# picoKey_230406.net
KiCad netlist of a schematic drawn in EAGLE
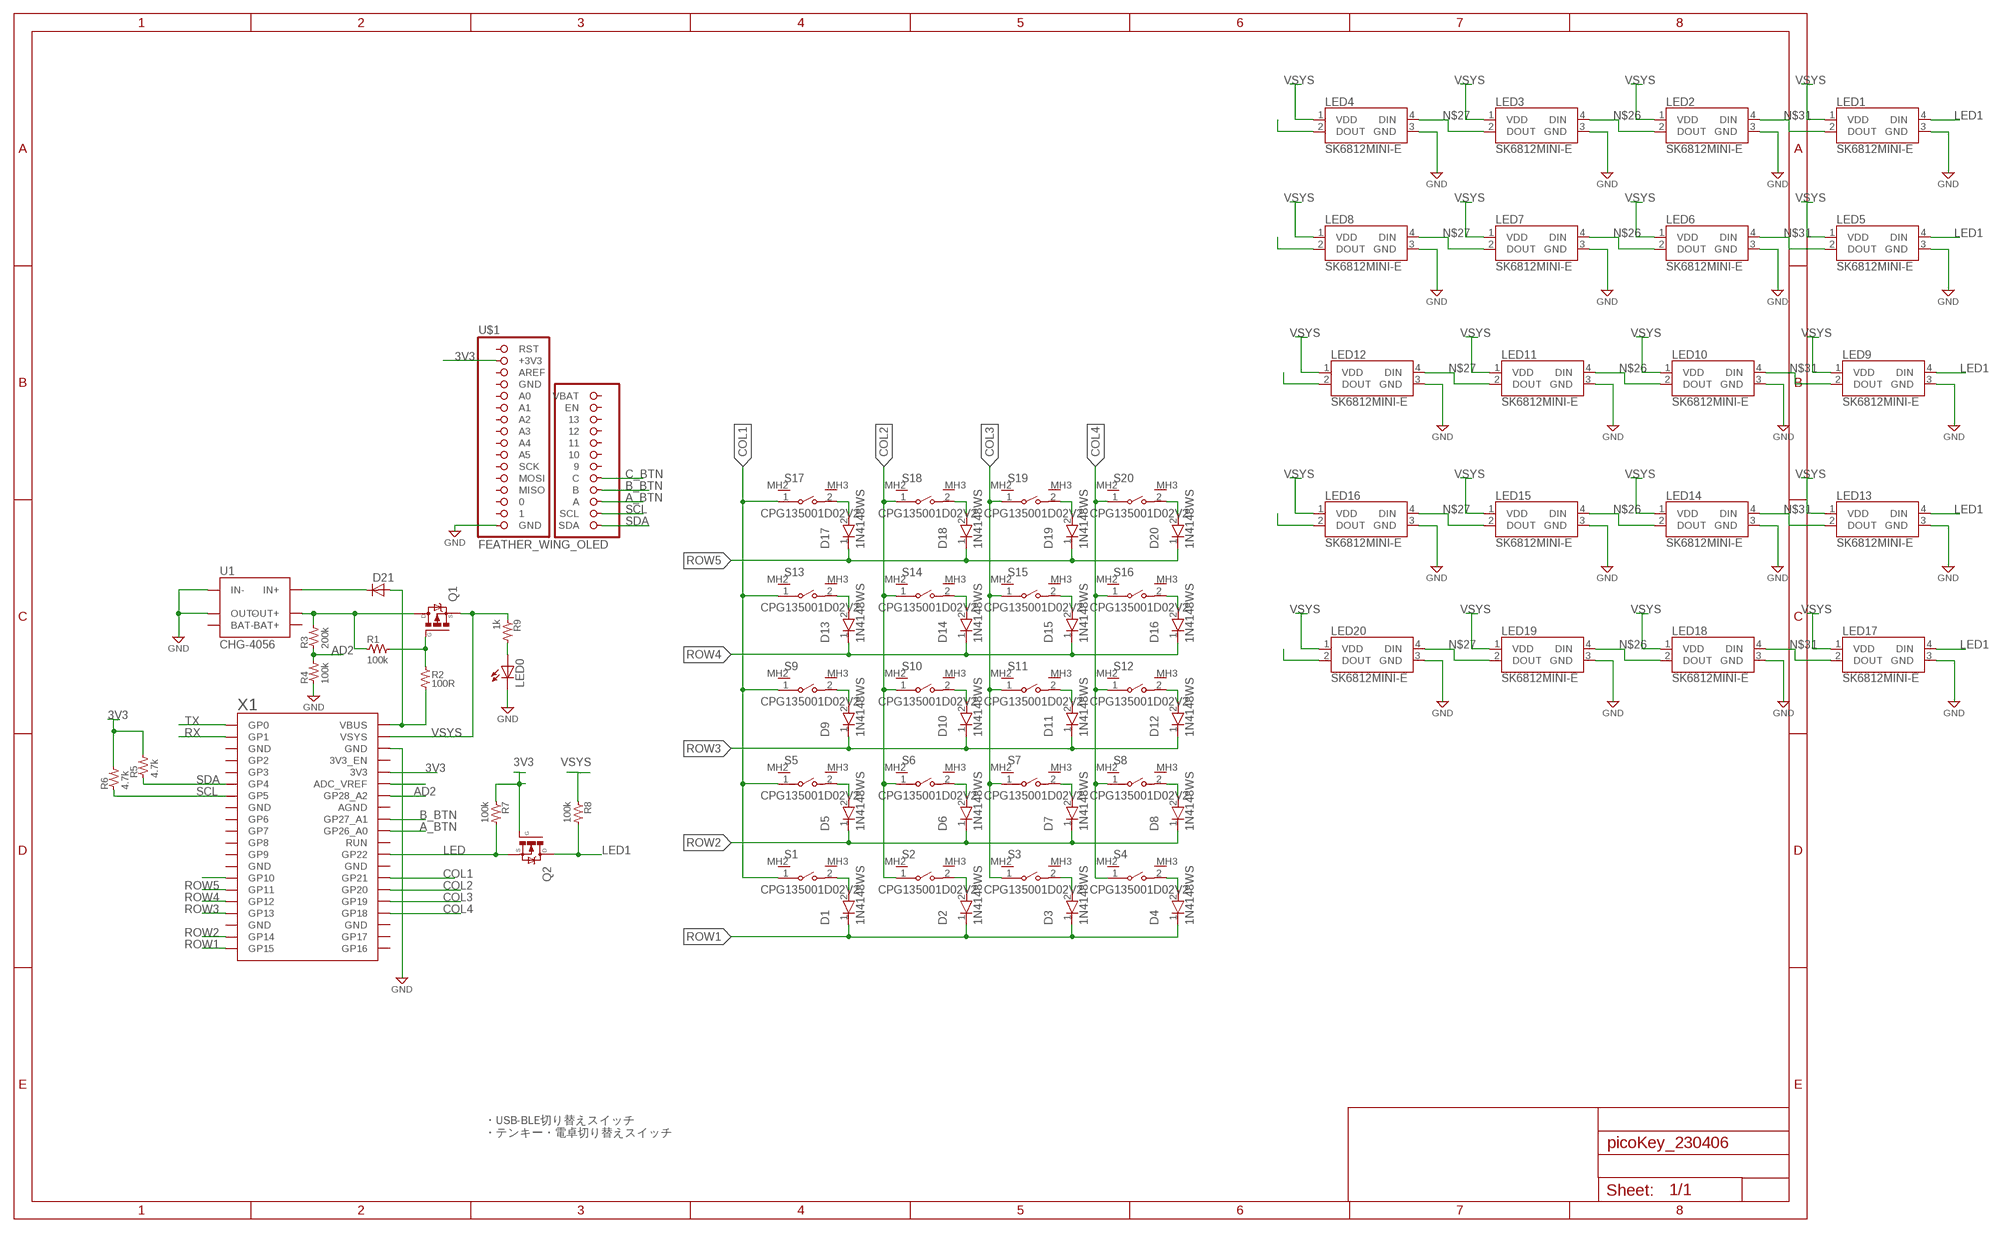
[diagram p0: schematic, sheet 1]

(export (version "E")
  (design (tool "Eeschema 10.0.6"))
  (components
    (comp (ref "D1")
      (value "1N4148WS")
      (footprint "eagle-import:SODFL2512X90N")
      (fields (field (name "MOUSER_PART_NUMBER") "512-1N4148WS"))
      (libsource (lib "eagle-import") (part "1N4148WS"))
    )
    (comp (ref "D2")
      (value "1N4148WS")
      (footprint "eagle-import:SODFL2512X90N")
      (fields (field (name "MOUSER_PART_NUMBER") "512-1N4148WS"))
      (libsource (lib "eagle-import") (part "1N4148WS"))
    )
    (comp (ref "D3")
      (value "1N4148WS")
      (footprint "eagle-import:SODFL2512X90N")
      (fields (field (name "MOUSER_PART_NUMBER") "512-1N4148WS"))
      (libsource (lib "eagle-import") (part "1N4148WS"))
    )
    (comp (ref "D4")
      (value "1N4148WS")
      (footprint "eagle-import:SODFL2512X90N")
      (fields (field (name "MOUSER_PART_NUMBER") "512-1N4148WS"))
      (libsource (lib "eagle-import") (part "1N4148WS"))
    )
    (comp (ref "D5")
      (value "1N4148WS")
      (footprint "eagle-import:SODFL2512X90N")
      (fields (field (name "MOUSER_PART_NUMBER") "512-1N4148WS"))
      (libsource (lib "eagle-import") (part "1N4148WS"))
    )
    (comp (ref "D6")
      (value "1N4148WS")
      (footprint "eagle-import:SODFL2512X90N")
      (fields (field (name "MOUSER_PART_NUMBER") "512-1N4148WS"))
      (libsource (lib "eagle-import") (part "1N4148WS"))
    )
    (comp (ref "D7")
      (value "1N4148WS")
      (footprint "eagle-import:SODFL2512X90N")
      (fields (field (name "MOUSER_PART_NUMBER") "512-1N4148WS"))
      (libsource (lib "eagle-import") (part "1N4148WS"))
    )
    (comp (ref "D8")
      (value "1N4148WS")
      (footprint "eagle-import:SODFL2512X90N")
      (fields (field (name "MOUSER_PART_NUMBER") "512-1N4148WS"))
      (libsource (lib "eagle-import") (part "1N4148WS"))
    )
    (comp (ref "D9")
      (value "1N4148WS")
      (footprint "eagle-import:SODFL2512X90N")
      (fields (field (name "MOUSER_PART_NUMBER") "512-1N4148WS"))
      (libsource (lib "eagle-import") (part "1N4148WS"))
    )
    (comp (ref "D10")
      (value "1N4148WS")
      (footprint "eagle-import:SODFL2512X90N")
      (fields (field (name "MOUSER_PART_NUMBER") "512-1N4148WS"))
      (libsource (lib "eagle-import") (part "1N4148WS"))
    )
    (comp (ref "D11")
      (value "1N4148WS")
      (footprint "eagle-import:SODFL2512X90N")
      (fields (field (name "MOUSER_PART_NUMBER") "512-1N4148WS"))
      (libsource (lib "eagle-import") (part "1N4148WS"))
    )
    (comp (ref "D12")
      (value "1N4148WS")
      (footprint "eagle-import:SODFL2512X90N")
      (fields (field (name "MOUSER_PART_NUMBER") "512-1N4148WS"))
      (libsource (lib "eagle-import") (part "1N4148WS"))
    )
    (comp (ref "D13")
      (value "1N4148WS")
      (footprint "eagle-import:SODFL2512X90N")
      (fields (field (name "MOUSER_PART_NUMBER") "512-1N4148WS"))
      (libsource (lib "eagle-import") (part "1N4148WS"))
    )
    (comp (ref "D14")
      (value "1N4148WS")
      (footprint "eagle-import:SODFL2512X90N")
      (fields (field (name "MOUSER_PART_NUMBER") "512-1N4148WS"))
      (libsource (lib "eagle-import") (part "1N4148WS"))
    )
    (comp (ref "D15")
      (value "1N4148WS")
      (footprint "eagle-import:SODFL2512X90N")
      (fields (field (name "MOUSER_PART_NUMBER") "512-1N4148WS"))
      (libsource (lib "eagle-import") (part "1N4148WS"))
    )
    (comp (ref "D16")
      (value "1N4148WS")
      (footprint "eagle-import:SODFL2512X90N")
      (fields (field (name "MOUSER_PART_NUMBER") "512-1N4148WS"))
      (libsource (lib "eagle-import") (part "1N4148WS"))
    )
    (comp (ref "D17")
      (value "1N4148WS")
      (footprint "eagle-import:SODFL2512X90N")
      (fields (field (name "MOUSER_PART_NUMBER") "512-1N4148WS"))
      (libsource (lib "eagle-import") (part "1N4148WS"))
    )
    (comp (ref "D18")
      (value "1N4148WS")
      (footprint "eagle-import:SODFL2512X90N")
      (fields (field (name "MOUSER_PART_NUMBER") "512-1N4148WS"))
      (libsource (lib "eagle-import") (part "1N4148WS"))
    )
    (comp (ref "D19")
      (value "1N4148WS")
      (footprint "eagle-import:SODFL2512X90N")
      (fields (field (name "MOUSER_PART_NUMBER") "512-1N4148WS"))
      (libsource (lib "eagle-import") (part "1N4148WS"))
    )
    (comp (ref "D20")
      (value "1N4148WS")
      (footprint "eagle-import:SODFL2512X90N")
      (fields (field (name "MOUSER_PART_NUMBER") "512-1N4148WS"))
      (libsource (lib "eagle-import") (part "1N4148WS"))
    )
    (comp (ref "D21")
      (value "DIODE123")
      (footprint "eagle-import:SOD-123")
      (libsource (lib "eagle-import") (part "DIODE123"))
    )
    (comp (ref "LED0")
      (value "LEDCHIP-LED0603")
      (footprint "eagle-import:CHIP-LED0603")
      (libsource (lib "eagle-import") (part "LEDCHIP-LED0603"))
    )
    (comp (ref "LED1")
      (value "SK6812MINI-E")
      (footprint "eagle-import:SK6812MINIE")
      (libsource (lib "eagle-import") (part "SK6812MINI-E"))
    )
    (comp (ref "LED2")
      (value "SK6812MINI-E")
      (footprint "eagle-import:SK6812MINIE")
      (libsource (lib "eagle-import") (part "SK6812MINI-E"))
    )
    (comp (ref "LED3")
      (value "SK6812MINI-E")
      (footprint "eagle-import:SK6812MINIE")
      (libsource (lib "eagle-import") (part "SK6812MINI-E"))
    )
    (comp (ref "LED4")
      (value "SK6812MINI-E")
      (footprint "eagle-import:SK6812MINIE")
      (libsource (lib "eagle-import") (part "SK6812MINI-E"))
    )
    (comp (ref "LED5")
      (value "SK6812MINI-E")
      (footprint "eagle-import:SK6812MINIE")
      (libsource (lib "eagle-import") (part "SK6812MINI-E"))
    )
    (comp (ref "LED6")
      (value "SK6812MINI-E")
      (footprint "eagle-import:SK6812MINIE")
      (libsource (lib "eagle-import") (part "SK6812MINI-E"))
    )
    (comp (ref "LED7")
      (value "SK6812MINI-E")
      (footprint "eagle-import:SK6812MINIE")
      (libsource (lib "eagle-import") (part "SK6812MINI-E"))
    )
    (comp (ref "LED8")
      (value "SK6812MINI-E")
      (footprint "eagle-import:SK6812MINIE")
      (libsource (lib "eagle-import") (part "SK6812MINI-E"))
    )
    (comp (ref "LED9")
      (value "SK6812MINI-E")
      (footprint "eagle-import:SK6812MINIE")
      (libsource (lib "eagle-import") (part "SK6812MINI-E"))
    )
    (comp (ref "LED10")
      (value "SK6812MINI-E")
      (footprint "eagle-import:SK6812MINIE")
      (libsource (lib "eagle-import") (part "SK6812MINI-E"))
    )
    (comp (ref "LED11")
      (value "SK6812MINI-E")
      (footprint "eagle-import:SK6812MINIE")
      (libsource (lib "eagle-import") (part "SK6812MINI-E"))
    )
    (comp (ref "LED12")
      (value "SK6812MINI-E")
      (footprint "eagle-import:SK6812MINIE")
      (libsource (lib "eagle-import") (part "SK6812MINI-E"))
    )
    (comp (ref "LED13")
      (value "SK6812MINI-E")
      (footprint "eagle-import:SK6812MINIE")
      (libsource (lib "eagle-import") (part "SK6812MINI-E"))
    )
    (comp (ref "LED14")
      (value "SK6812MINI-E")
      (footprint "eagle-import:SK6812MINIE")
      (libsource (lib "eagle-import") (part "SK6812MINI-E"))
    )
    (comp (ref "LED15")
      (value "SK6812MINI-E")
      (footprint "eagle-import:SK6812MINIE")
      (libsource (lib "eagle-import") (part "SK6812MINI-E"))
    )
    (comp (ref "LED16")
      (value "SK6812MINI-E")
      (footprint "eagle-import:SK6812MINIE")
      (libsource (lib "eagle-import") (part "SK6812MINI-E"))
    )
    (comp (ref "LED17")
      (value "SK6812MINI-E")
      (footprint "eagle-import:SK6812MINIE")
      (libsource (lib "eagle-import") (part "SK6812MINI-E"))
    )
    (comp (ref "LED18")
      (value "SK6812MINI-E")
      (footprint "eagle-import:SK6812MINIE")
      (libsource (lib "eagle-import") (part "SK6812MINI-E"))
    )
    (comp (ref "LED19")
      (value "SK6812MINI-E")
      (footprint "eagle-import:SK6812MINIE")
      (libsource (lib "eagle-import") (part "SK6812MINI-E"))
    )
    (comp (ref "LED20")
      (value "SK6812MINI-E")
      (footprint "eagle-import:SK6812MINIE")
      (libsource (lib "eagle-import") (part "SK6812MINI-E"))
    )
    (comp (ref "Q1")
      (value "MOSFET-P")
      (footprint "eagle-import:SOT-23")
      (libsource (lib "eagle-import") (part "MOSFET-P"))
    )
    (comp (ref "Q2")
      (value "MOSFET-NSOT-23")
      (footprint "eagle-import:SOT-23")
      (libsource (lib "eagle-import") (part "MOSFET-NSOT-23"))
    )
    (comp (ref "R1")
      (value "100k")
      (footprint "eagle-import:R0603")
      (libsource (lib "eagle-import") (part "R_0603"))
    )
    (comp (ref "R2")
      (value "100R")
      (footprint "eagle-import:R0603")
      (libsource (lib "eagle-import") (part "R_0603"))
    )
    (comp (ref "R3")
      (value "200k")
      (footprint "eagle-import:R0603")
      (libsource (lib "eagle-import") (part "R_0603"))
    )
    (comp (ref "R4")
      (value "100k")
      (footprint "eagle-import:R0603")
      (libsource (lib "eagle-import") (part "R_0603"))
    )
    (comp (ref "R5")
      (value "4.7k")
      (footprint "eagle-import:R0603")
      (libsource (lib "eagle-import") (part "R_0603"))
    )
    (comp (ref "R6")
      (value "4.7k")
      (footprint "eagle-import:R0603")
      (libsource (lib "eagle-import") (part "R_0603"))
    )
    (comp (ref "R7")
      (value "100k")
      (footprint "eagle-import:R0603")
      (libsource (lib "eagle-import") (part "R_0603"))
    )
    (comp (ref "R8")
      (value "100k")
      (footprint "eagle-import:R0603")
      (libsource (lib "eagle-import") (part "R_0603"))
    )
    (comp (ref "R9")
      (value "1k")
      (footprint "eagle-import:R0603")
      (libsource (lib "eagle-import") (part "R_0603"))
    )
    (comp (ref "S1")
      (value "CPG135001D02V2")
      (footprint "eagle-import:KAILH_CHOC_V2")
      (libsource (lib "eagle-import") (part "CPG135001D02V2"))
    )
    (comp (ref "S2")
      (value "CPG135001D02V2")
      (footprint "eagle-import:KAILH_CHOC_V2")
      (libsource (lib "eagle-import") (part "CPG135001D02V2"))
    )
    (comp (ref "S3")
      (value "CPG135001D02V2")
      (footprint "eagle-import:KAILH_CHOC_V2")
      (libsource (lib "eagle-import") (part "CPG135001D02V2"))
    )
    (comp (ref "S4")
      (value "CPG135001D02V2")
      (footprint "eagle-import:KAILH_CHOC_V2")
      (libsource (lib "eagle-import") (part "CPG135001D02V2"))
    )
    (comp (ref "S5")
      (value "CPG135001D02V2")
      (footprint "eagle-import:KAILH_CHOC_V2")
      (libsource (lib "eagle-import") (part "CPG135001D02V2"))
    )
    (comp (ref "S6")
      (value "CPG135001D02V2")
      (footprint "eagle-import:KAILH_CHOC_V2")
      (libsource (lib "eagle-import") (part "CPG135001D02V2"))
    )
    (comp (ref "S7")
      (value "CPG135001D02V2")
      (footprint "eagle-import:KAILH_CHOC_V2")
      (libsource (lib "eagle-import") (part "CPG135001D02V2"))
    )
    (comp (ref "S8")
      (value "CPG135001D02V2")
      (footprint "eagle-import:KAILH_CHOC_V2")
      (libsource (lib "eagle-import") (part "CPG135001D02V2"))
    )
    (comp (ref "S9")
      (value "CPG135001D02V2")
      (footprint "eagle-import:KAILH_CHOC_V2")
      (libsource (lib "eagle-import") (part "CPG135001D02V2"))
    )
    (comp (ref "S10")
      (value "CPG135001D02V2")
      (footprint "eagle-import:KAILH_CHOC_V2")
      (libsource (lib "eagle-import") (part "CPG135001D02V2"))
    )
    (comp (ref "S11")
      (value "CPG135001D02V2")
      (footprint "eagle-import:KAILH_CHOC_V2")
      (libsource (lib "eagle-import") (part "CPG135001D02V2"))
    )
    (comp (ref "S12")
      (value "CPG135001D02V2")
      (footprint "eagle-import:KAILH_CHOC_V2")
      (libsource (lib "eagle-import") (part "CPG135001D02V2"))
    )
    (comp (ref "S13")
      (value "CPG135001D02V2")
      (footprint "eagle-import:KAILH_CHOC_V2")
      (libsource (lib "eagle-import") (part "CPG135001D02V2"))
    )
    (comp (ref "S14")
      (value "CPG135001D02V2")
      (footprint "eagle-import:KAILH_CHOC_V2")
      (libsource (lib "eagle-import") (part "CPG135001D02V2"))
    )
    (comp (ref "S15")
      (value "CPG135001D02V2")
      (footprint "eagle-import:KAILH_CHOC_V2")
      (libsource (lib "eagle-import") (part "CPG135001D02V2"))
    )
    (comp (ref "S16")
      (value "CPG135001D02V2")
      (footprint "eagle-import:KAILH_CHOC_V2")
      (libsource (lib "eagle-import") (part "CPG135001D02V2"))
    )
    (comp (ref "S17")
      (value "CPG135001D02V2")
      (footprint "eagle-import:KAILH_CHOC_V2")
      (libsource (lib "eagle-import") (part "CPG135001D02V2"))
    )
    (comp (ref "S18")
      (value "CPG135001D02V2")
      (footprint "eagle-import:KAILH_CHOC_V2")
      (libsource (lib "eagle-import") (part "CPG135001D02V2"))
    )
    (comp (ref "S19")
      (value "CPG135001D02V2")
      (footprint "eagle-import:KAILH_CHOC_V2")
      (libsource (lib "eagle-import") (part "CPG135001D02V2"))
    )
    (comp (ref "S20")
      (value "CPG135001D02V2")
      (footprint "eagle-import:KAILH_CHOC_V2")
      (libsource (lib "eagle-import") (part "CPG135001D02V2"))
    )
    (comp (ref "U$1")
      (value "FEATHER_WING_OLED")
      (footprint "eagle-import:FEATHER_WING_OLED")
      (libsource (lib "eagle-import") (part "FEATHER_WING_OLED"))
    )
    (comp (ref "U1")
      (value "CHG-4056")
      (footprint "eagle-import:CHG-4056")
      (libsource (lib "eagle-import") (part "CHG-4056"))
    )
    (comp (ref "X1")
      (value "RASPBERRYPI_PICO_RPI_PICO_MY-MY")
      (footprint "eagle-import:RASPBERRYPI_PICO_RPI_PICO_MY")
      (libsource (lib "eagle-import") (part "RASPBERRYPI_PICO_RPI_PICO_MY-MY"))
    )
  )
  (nets
    (net (code "1") (name "/3V3") (class "Default")
      (node (ref "Q2") (pin "3") (pinfunction "G_3") (pintype "passive"))
      (node (ref "R5") (pin "2") (pinfunction "2_2") (pintype "passive"))
      (node (ref "R6") (pin "2") (pinfunction "2_2") (pintype "passive"))
      (node (ref "R7") (pin "1") (pinfunction "1_1") (pintype "passive"))
      (node (ref "U$1") (pin "15") (pinfunction "+3V3_15") (pintype "passive"))
      (node (ref "X1") (pin "3V3") (pinfunction "3V3_3V3") (pintype "bidirectional"))
    )
    (net (code "2") (name "/AD2") (class "Default")
      (node (ref "R3") (pin "1") (pinfunction "1_1") (pintype "passive"))
      (node (ref "R4") (pin "2") (pinfunction "2_2") (pintype "passive"))
      (node (ref "X1") (pin "GP28_A2") (pinfunction "GP28_A2_GP28_A2") (pintype "bidirectional"))
    )
    (net (code "3") (name "/A_BTN") (class "Default")
      (node (ref "U$1") (pin "26") (pinfunction "A_26") (pintype "passive"))
      (node (ref "X1") (pin "GP26_A0") (pinfunction "GP26_A0_GP26_A0") (pintype "bidirectional"))
    )
    (net (code "4") (name "/B_BTN") (class "Default")
      (node (ref "U$1") (pin "25") (pinfunction "B_25") (pintype "passive"))
      (node (ref "X1") (pin "GP27_A1") (pinfunction "GP27_A1_GP27_A1") (pintype "bidirectional"))
    )
    (net (code "5") (name "/C_BTN") (class "Default")
      (node (ref "U$1") (pin "24") (pinfunction "C_24") (pintype "passive"))
    )
    (net (code "6") (name "/LED") (class "Default")
      (node (ref "Q2") (pin "1") (pinfunction "S_1") (pintype "passive"))
      (node (ref "R7") (pin "2") (pinfunction "2_2") (pintype "passive"))
      (node (ref "X1") (pin "GP22") (pinfunction "GP22_GP22") (pintype "bidirectional"))
    )
    (net (code "7") (name "/LED1") (class "Default")
      (node (ref "LED1") (pin "4") (pinfunction "DIN_4") (pintype "bidirectional"))
      (node (ref "LED13") (pin "4") (pinfunction "DIN_4") (pintype "bidirectional"))
      (node (ref "LED17") (pin "4") (pinfunction "DIN_4") (pintype "bidirectional"))
      (node (ref "LED5") (pin "4") (pinfunction "DIN_4") (pintype "bidirectional"))
      (node (ref "LED9") (pin "4") (pinfunction "DIN_4") (pintype "bidirectional"))
      (node (ref "Q2") (pin "2") (pinfunction "D_2") (pintype "passive"))
      (node (ref "R8") (pin "2") (pinfunction "2_2") (pintype "passive"))
    )
    (net (code "8") (name "/N$26") (class "Default")
      (node (ref "LED10") (pin "2") (pinfunction "DOUT_2") (pintype "bidirectional"))
      (node (ref "LED11") (pin "4") (pinfunction "DIN_4") (pintype "bidirectional"))
      (node (ref "LED14") (pin "2") (pinfunction "DOUT_2") (pintype "bidirectional"))
      (node (ref "LED15") (pin "4") (pinfunction "DIN_4") (pintype "bidirectional"))
      (node (ref "LED18") (pin "2") (pinfunction "DOUT_2") (pintype "bidirectional"))
      (node (ref "LED19") (pin "4") (pinfunction "DIN_4") (pintype "bidirectional"))
      (node (ref "LED2") (pin "2") (pinfunction "DOUT_2") (pintype "bidirectional"))
      (node (ref "LED3") (pin "4") (pinfunction "DIN_4") (pintype "bidirectional"))
      (node (ref "LED6") (pin "2") (pinfunction "DOUT_2") (pintype "bidirectional"))
      (node (ref "LED7") (pin "4") (pinfunction "DIN_4") (pintype "bidirectional"))
    )
    (net (code "9") (name "/N$27") (class "Default")
      (node (ref "LED11") (pin "2") (pinfunction "DOUT_2") (pintype "bidirectional"))
      (node (ref "LED12") (pin "4") (pinfunction "DIN_4") (pintype "bidirectional"))
      (node (ref "LED15") (pin "2") (pinfunction "DOUT_2") (pintype "bidirectional"))
      (node (ref "LED16") (pin "4") (pinfunction "DIN_4") (pintype "bidirectional"))
      (node (ref "LED19") (pin "2") (pinfunction "DOUT_2") (pintype "bidirectional"))
      (node (ref "LED20") (pin "4") (pinfunction "DIN_4") (pintype "bidirectional"))
      (node (ref "LED3") (pin "2") (pinfunction "DOUT_2") (pintype "bidirectional"))
      (node (ref "LED4") (pin "4") (pinfunction "DIN_4") (pintype "bidirectional"))
      (node (ref "LED7") (pin "2") (pinfunction "DOUT_2") (pintype "bidirectional"))
      (node (ref "LED8") (pin "4") (pinfunction "DIN_4") (pintype "bidirectional"))
    )
    (net (code "10") (name "/N$31") (class "Default")
      (node (ref "LED1") (pin "2") (pinfunction "DOUT_2") (pintype "bidirectional"))
      (node (ref "LED10") (pin "4") (pinfunction "DIN_4") (pintype "bidirectional"))
      (node (ref "LED13") (pin "2") (pinfunction "DOUT_2") (pintype "bidirectional"))
      (node (ref "LED14") (pin "4") (pinfunction "DIN_4") (pintype "bidirectional"))
      (node (ref "LED17") (pin "2") (pinfunction "DOUT_2") (pintype "bidirectional"))
      (node (ref "LED18") (pin "4") (pinfunction "DIN_4") (pintype "bidirectional"))
      (node (ref "LED2") (pin "4") (pinfunction "DIN_4") (pintype "bidirectional"))
      (node (ref "LED5") (pin "2") (pinfunction "DOUT_2") (pintype "bidirectional"))
      (node (ref "LED6") (pin "4") (pinfunction "DIN_4") (pintype "bidirectional"))
      (node (ref "LED9") (pin "2") (pinfunction "DOUT_2") (pintype "bidirectional"))
    )
    (net (code "11") (name "/RX") (class "Default")
      (node (ref "X1") (pin "GP1") (pinfunction "GP1_GP1") (pintype "bidirectional"))
    )
    (net (code "12") (name "/SCL") (class "Default")
      (node (ref "R6") (pin "1") (pinfunction "1_1") (pintype "passive"))
      (node (ref "U$1") (pin "27") (pinfunction "SCL_27") (pintype "passive"))
      (node (ref "X1") (pin "GP5") (pinfunction "GP5_GP5") (pintype "bidirectional"))
    )
    (net (code "13") (name "/SDA") (class "Default")
      (node (ref "R5") (pin "1") (pinfunction "1_1") (pintype "passive"))
      (node (ref "U$1") (pin "28") (pinfunction "SDA_28") (pintype "passive"))
      (node (ref "X1") (pin "GP4") (pinfunction "GP4_GP4") (pintype "bidirectional"))
    )
    (net (code "14") (name "/TX") (class "Default")
      (node (ref "X1") (pin "GP0") (pinfunction "GP0_GP0") (pintype "bidirectional"))
    )
    (net (code "15") (name "/VSYS") (class "Default")
      (node (ref "LED1") (pin "1") (pinfunction "VDD_1") (pintype "bidirectional"))
      (node (ref "LED10") (pin "1") (pinfunction "VDD_1") (pintype "bidirectional"))
      (node (ref "LED11") (pin "1") (pinfunction "VDD_1") (pintype "bidirectional"))
      (node (ref "LED12") (pin "1") (pinfunction "VDD_1") (pintype "bidirectional"))
      (node (ref "LED13") (pin "1") (pinfunction "VDD_1") (pintype "bidirectional"))
      (node (ref "LED14") (pin "1") (pinfunction "VDD_1") (pintype "bidirectional"))
      (node (ref "LED15") (pin "1") (pinfunction "VDD_1") (pintype "bidirectional"))
      (node (ref "LED16") (pin "1") (pinfunction "VDD_1") (pintype "bidirectional"))
      (node (ref "LED17") (pin "1") (pinfunction "VDD_1") (pintype "bidirectional"))
      (node (ref "LED18") (pin "1") (pinfunction "VDD_1") (pintype "bidirectional"))
      (node (ref "LED19") (pin "1") (pinfunction "VDD_1") (pintype "bidirectional"))
      (node (ref "LED2") (pin "1") (pinfunction "VDD_1") (pintype "bidirectional"))
      (node (ref "LED20") (pin "1") (pinfunction "VDD_1") (pintype "bidirectional"))
      (node (ref "LED3") (pin "1") (pinfunction "VDD_1") (pintype "bidirectional"))
      (node (ref "LED4") (pin "1") (pinfunction "VDD_1") (pintype "bidirectional"))
      (node (ref "LED5") (pin "1") (pinfunction "VDD_1") (pintype "bidirectional"))
      (node (ref "LED6") (pin "1") (pinfunction "VDD_1") (pintype "bidirectional"))
      (node (ref "LED7") (pin "1") (pinfunction "VDD_1") (pintype "bidirectional"))
      (node (ref "LED8") (pin "1") (pinfunction "VDD_1") (pintype "bidirectional"))
      (node (ref "LED9") (pin "1") (pinfunction "VDD_1") (pintype "bidirectional"))
      (node (ref "Q1") (pin "1") (pinfunction "S_1") (pintype "passive"))
      (node (ref "R8") (pin "1") (pinfunction "1_1") (pintype "passive"))
      (node (ref "R9") (pin "1") (pinfunction "1_1") (pintype "passive"))
      (node (ref "X1") (pin "VSYS") (pinfunction "VSYS_VSYS") (pintype "bidirectional"))
    )
    (net (code "16") (name "COL1") (class "Default")
      (node (ref "S1") (pin "1") (pinfunction "1_1") (pintype "bidirectional"))
      (node (ref "S13") (pin "1") (pinfunction "1_1") (pintype "bidirectional"))
      (node (ref "S17") (pin "1") (pinfunction "1_1") (pintype "bidirectional"))
      (node (ref "S5") (pin "1") (pinfunction "1_1") (pintype "bidirectional"))
      (node (ref "S9") (pin "1") (pinfunction "1_1") (pintype "bidirectional"))
      (node (ref "X1") (pin "GP21") (pinfunction "GP21_GP21") (pintype "bidirectional"))
    )
    (net (code "17") (name "COL2") (class "Default")
      (node (ref "S10") (pin "1") (pinfunction "1_1") (pintype "bidirectional"))
      (node (ref "S14") (pin "1") (pinfunction "1_1") (pintype "bidirectional"))
      (node (ref "S18") (pin "1") (pinfunction "1_1") (pintype "bidirectional"))
      (node (ref "S2") (pin "1") (pinfunction "1_1") (pintype "bidirectional"))
      (node (ref "S6") (pin "1") (pinfunction "1_1") (pintype "bidirectional"))
      (node (ref "X1") (pin "GP20") (pinfunction "GP20_GP20") (pintype "bidirectional"))
    )
    (net (code "18") (name "COL3") (class "Default")
      (node (ref "S11") (pin "1") (pinfunction "1_1") (pintype "bidirectional"))
      (node (ref "S15") (pin "1") (pinfunction "1_1") (pintype "bidirectional"))
      (node (ref "S19") (pin "1") (pinfunction "1_1") (pintype "bidirectional"))
      (node (ref "S3") (pin "1") (pinfunction "1_1") (pintype "bidirectional"))
      (node (ref "S7") (pin "1") (pinfunction "1_1") (pintype "bidirectional"))
      (node (ref "X1") (pin "GP19") (pinfunction "GP19_GP19") (pintype "bidirectional"))
    )
    (net (code "19") (name "COL4") (class "Default")
      (node (ref "S12") (pin "1") (pinfunction "1_1") (pintype "bidirectional"))
      (node (ref "S16") (pin "1") (pinfunction "1_1") (pintype "bidirectional"))
      (node (ref "S20") (pin "1") (pinfunction "1_1") (pintype "bidirectional"))
      (node (ref "S4") (pin "1") (pinfunction "1_1") (pintype "bidirectional"))
      (node (ref "S8") (pin "1") (pinfunction "1_1") (pintype "bidirectional"))
      (node (ref "X1") (pin "GP18") (pinfunction "GP18_GP18") (pintype "bidirectional"))
    )
    (net (code "20") (name "G") (class "Default")
      (node (ref "LED0") (pin "C") (pinfunction "C_C") (pintype "passive"))
      (node (ref "LED1") (pin "3") (pinfunction "GND_3") (pintype "bidirectional"))
      (node (ref "LED10") (pin "3") (pinfunction "GND_3") (pintype "bidirectional"))
      (node (ref "LED11") (pin "3") (pinfunction "GND_3") (pintype "bidirectional"))
      (node (ref "LED12") (pin "3") (pinfunction "GND_3") (pintype "bidirectional"))
      (node (ref "LED13") (pin "3") (pinfunction "GND_3") (pintype "bidirectional"))
      (node (ref "LED14") (pin "3") (pinfunction "GND_3") (pintype "bidirectional"))
      (node (ref "LED15") (pin "3") (pinfunction "GND_3") (pintype "bidirectional"))
      (node (ref "LED16") (pin "3") (pinfunction "GND_3") (pintype "bidirectional"))
      (node (ref "LED17") (pin "3") (pinfunction "GND_3") (pintype "bidirectional"))
      (node (ref "LED18") (pin "3") (pinfunction "GND_3") (pintype "bidirectional"))
      (node (ref "LED19") (pin "3") (pinfunction "GND_3") (pintype "bidirectional"))
      (node (ref "LED2") (pin "3") (pinfunction "GND_3") (pintype "bidirectional"))
      (node (ref "LED20") (pin "3") (pinfunction "GND_3") (pintype "bidirectional"))
      (node (ref "LED3") (pin "3") (pinfunction "GND_3") (pintype "bidirectional"))
      (node (ref "LED4") (pin "3") (pinfunction "GND_3") (pintype "bidirectional"))
      (node (ref "LED5") (pin "3") (pinfunction "GND_3") (pintype "bidirectional"))
      (node (ref "LED6") (pin "3") (pinfunction "GND_3") (pintype "bidirectional"))
      (node (ref "LED7") (pin "3") (pinfunction "GND_3") (pintype "bidirectional"))
      (node (ref "LED8") (pin "3") (pinfunction "GND_3") (pintype "bidirectional"))
      (node (ref "LED9") (pin "3") (pinfunction "GND_3") (pintype "bidirectional"))
      (node (ref "R4") (pin "1") (pinfunction "1_1") (pintype "passive"))
      (node (ref "U$1") (pin "1") (pinfunction "GND_1") (pintype "passive"))
      (node (ref "U1") (pin "IN-") (pinfunction "IN-_IN-") (pintype "bidirectional"))
      (node (ref "U1") (pin "OUT-") (pinfunction "OUT-_OUT-") (pintype "bidirectional"))
      (node (ref "X1") (pin "GND@8") (pinfunction "GND_GND@8") (pintype "bidirectional"))
    )
    (net (code "21") (name "Net-(D1-A)") (class "Default")
      (node (ref "D1") (pin "2") (pinfunction "A_2") (pintype "bidirectional"))
      (node (ref "S1") (pin "2") (pinfunction "2_2") (pintype "bidirectional"))
    )
    (net (code "22") (name "Net-(D2-A)") (class "Default")
      (node (ref "D2") (pin "2") (pinfunction "A_2") (pintype "bidirectional"))
      (node (ref "S2") (pin "2") (pinfunction "2_2") (pintype "bidirectional"))
    )
    (net (code "23") (name "Net-(D3-A)") (class "Default")
      (node (ref "D3") (pin "2") (pinfunction "A_2") (pintype "bidirectional"))
      (node (ref "S3") (pin "2") (pinfunction "2_2") (pintype "bidirectional"))
    )
    (net (code "24") (name "Net-(D4-A)") (class "Default")
      (node (ref "D4") (pin "2") (pinfunction "A_2") (pintype "bidirectional"))
      (node (ref "S4") (pin "2") (pinfunction "2_2") (pintype "bidirectional"))
    )
    (net (code "25") (name "Net-(D5-A)") (class "Default")
      (node (ref "D5") (pin "2") (pinfunction "A_2") (pintype "bidirectional"))
      (node (ref "S5") (pin "2") (pinfunction "2_2") (pintype "bidirectional"))
    )
    (net (code "26") (name "Net-(D6-A)") (class "Default")
      (node (ref "D6") (pin "2") (pinfunction "A_2") (pintype "bidirectional"))
      (node (ref "S6") (pin "2") (pinfunction "2_2") (pintype "bidirectional"))
    )
    (net (code "27") (name "Net-(D7-A)") (class "Default")
      (node (ref "D7") (pin "2") (pinfunction "A_2") (pintype "bidirectional"))
      (node (ref "S7") (pin "2") (pinfunction "2_2") (pintype "bidirectional"))
    )
    (net (code "28") (name "Net-(D8-A)") (class "Default")
      (node (ref "D8") (pin "2") (pinfunction "A_2") (pintype "bidirectional"))
      (node (ref "S8") (pin "2") (pinfunction "2_2") (pintype "bidirectional"))
    )
    (net (code "29") (name "Net-(D9-A)") (class "Default")
      (node (ref "D9") (pin "2") (pinfunction "A_2") (pintype "bidirectional"))
      (node (ref "S9") (pin "2") (pinfunction "2_2") (pintype "bidirectional"))
    )
    (net (code "30") (name "Net-(D10-A)") (class "Default")
      (node (ref "D10") (pin "2") (pinfunction "A_2") (pintype "bidirectional"))
      (node (ref "S10") (pin "2") (pinfunction "2_2") (pintype "bidirectional"))
    )
    (net (code "31") (name "Net-(D11-A)") (class "Default")
      (node (ref "D11") (pin "2") (pinfunction "A_2") (pintype "bidirectional"))
      (node (ref "S11") (pin "2") (pinfunction "2_2") (pintype "bidirectional"))
    )
    (net (code "32") (name "Net-(D12-A)") (class "Default")
      (node (ref "D12") (pin "2") (pinfunction "A_2") (pintype "bidirectional"))
      (node (ref "S12") (pin "2") (pinfunction "2_2") (pintype "bidirectional"))
    )
    (net (code "33") (name "Net-(D13-A)") (class "Default")
      (node (ref "D13") (pin "2") (pinfunction "A_2") (pintype "bidirectional"))
      (node (ref "S13") (pin "2") (pinfunction "2_2") (pintype "bidirectional"))
    )
    (net (code "34") (name "Net-(D14-A)") (class "Default")
      (node (ref "D14") (pin "2") (pinfunction "A_2") (pintype "bidirectional"))
      (node (ref "S14") (pin "2") (pinfunction "2_2") (pintype "bidirectional"))
    )
    (net (code "35") (name "Net-(D15-A)") (class "Default")
      (node (ref "D15") (pin "2") (pinfunction "A_2") (pintype "bidirectional"))
      (node (ref "S15") (pin "2") (pinfunction "2_2") (pintype "bidirectional"))
    )
    (net (code "36") (name "Net-(D16-A)") (class "Default")
      (node (ref "D16") (pin "2") (pinfunction "A_2") (pintype "bidirectional"))
      (node (ref "S16") (pin "2") (pinfunction "2_2") (pintype "bidirectional"))
    )
    (net (code "37") (name "Net-(D17-A)") (class "Default")
      (node (ref "D17") (pin "2") (pinfunction "A_2") (pintype "bidirectional"))
      (node (ref "S17") (pin "2") (pinfunction "2_2") (pintype "bidirectional"))
    )
    (net (code "38") (name "Net-(D18-A)") (class "Default")
      (node (ref "D18") (pin "2") (pinfunction "A_2") (pintype "bidirectional"))
      (node (ref "S18") (pin "2") (pinfunction "2_2") (pintype "bidirectional"))
    )
    (net (code "39") (name "Net-(D19-A)") (class "Default")
      (node (ref "D19") (pin "2") (pinfunction "A_2") (pintype "bidirectional"))
      (node (ref "S19") (pin "2") (pinfunction "2_2") (pintype "bidirectional"))
    )
    (net (code "40") (name "Net-(D20-A)") (class "Default")
      (node (ref "D20") (pin "2") (pinfunction "A_2") (pintype "bidirectional"))
      (node (ref "S20") (pin "2") (pinfunction "2_2") (pintype "bidirectional"))
    )
    (net (code "41") (name "Net-(D21-C)") (class "Default")
      (node (ref "D21") (pin "K") (pinfunction "C_K") (pintype "passive"))
      (node (ref "U1") (pin "IN+") (pinfunction "IN+_IN+") (pintype "bidirectional"))
    )
    (net (code "42") (name "Net-(D21-PadA)") (class "Default")
      (node (ref "D21") (pin "A") (pinfunction "A_A") (pintype "passive"))
      (node (ref "R2") (pin "2") (pinfunction "2_2") (pintype "passive"))
      (node (ref "X1") (pin "VBUS") (pinfunction "VBUS_VBUS") (pintype "bidirectional"))
    )
    (net (code "43") (name "Net-(LED0-PadA)") (class "Default")
      (node (ref "LED0") (pin "A") (pinfunction "A_A") (pintype "passive"))
      (node (ref "R9") (pin "2") (pinfunction "2_2") (pintype "passive"))
    )
    (net (code "44") (name "Net-(Q1-D)") (class "Default")
      (node (ref "Q1") (pin "2") (pinfunction "D_2") (pintype "passive"))
      (node (ref "R1") (pin "1") (pinfunction "1_1") (pintype "passive"))
      (node (ref "R3") (pin "2") (pinfunction "2_2") (pintype "passive"))
      (node (ref "U1") (pin "OUT+") (pinfunction "OUT+_OUT+") (pintype "bidirectional"))
    )
    (net (code "45") (name "Net-(Q1-G)") (class "Default")
      (node (ref "Q1") (pin "3") (pinfunction "G_3") (pintype "passive"))
      (node (ref "R1") (pin "2") (pinfunction "2_2") (pintype "passive"))
      (node (ref "R2") (pin "1") (pinfunction "1_1") (pintype "passive"))
    )
    (net (code "46") (name "ROW1") (class "Default")
      (node (ref "D1") (pin "1") (pinfunction "K_1") (pintype "bidirectional"))
      (node (ref "D2") (pin "1") (pinfunction "K_1") (pintype "bidirectional"))
      (node (ref "D3") (pin "1") (pinfunction "K_1") (pintype "bidirectional"))
      (node (ref "D4") (pin "1") (pinfunction "K_1") (pintype "bidirectional"))
      (node (ref "X1") (pin "GP15") (pinfunction "GP15_GP15") (pintype "bidirectional"))
    )
    (net (code "47") (name "ROW2") (class "Default")
      (node (ref "D5") (pin "1") (pinfunction "K_1") (pintype "bidirectional"))
      (node (ref "D6") (pin "1") (pinfunction "K_1") (pintype "bidirectional"))
      (node (ref "D7") (pin "1") (pinfunction "K_1") (pintype "bidirectional"))
      (node (ref "D8") (pin "1") (pinfunction "K_1") (pintype "bidirectional"))
      (node (ref "X1") (pin "GP14") (pinfunction "GP14_GP14") (pintype "bidirectional"))
    )
    (net (code "48") (name "ROW3") (class "Default")
      (node (ref "D10") (pin "1") (pinfunction "K_1") (pintype "bidirectional"))
      (node (ref "D11") (pin "1") (pinfunction "K_1") (pintype "bidirectional"))
      (node (ref "D12") (pin "1") (pinfunction "K_1") (pintype "bidirectional"))
      (node (ref "D9") (pin "1") (pinfunction "K_1") (pintype "bidirectional"))
      (node (ref "X1") (pin "GP13") (pinfunction "GP13_GP13") (pintype "bidirectional"))
    )
    (net (code "49") (name "ROW4") (class "Default")
      (node (ref "D13") (pin "1") (pinfunction "K_1") (pintype "bidirectional"))
      (node (ref "D14") (pin "1") (pinfunction "K_1") (pintype "bidirectional"))
      (node (ref "D15") (pin "1") (pinfunction "K_1") (pintype "bidirectional"))
      (node (ref "D16") (pin "1") (pinfunction "K_1") (pintype "bidirectional"))
      (node (ref "X1") (pin "GP12") (pinfunction "GP12_GP12") (pintype "bidirectional"))
    )
    (net (code "50") (name "ROW5") (class "Default")
      (node (ref "D17") (pin "1") (pinfunction "K_1") (pintype "bidirectional"))
      (node (ref "D18") (pin "1") (pinfunction "K_1") (pintype "bidirectional"))
      (node (ref "D19") (pin "1") (pinfunction "K_1") (pintype "bidirectional"))
      (node (ref "D20") (pin "1") (pinfunction "K_1") (pintype "bidirectional"))
      (node (ref "X1") (pin "GP11") (pinfunction "GP11_GP11") (pintype "bidirectional"))
    )
    (net (code "51") (name "unconnected-(LED4-DOUT-Pad2)") (class "Default")
      (node (ref "LED4") (pin "2") (pinfunction "DOUT_2") (pintype "bidirectional"))
    )
    (net (code "52") (name "unconnected-(LED8-DOUT-Pad2)") (class "Default")
      (node (ref "LED8") (pin "2") (pinfunction "DOUT_2") (pintype "bidirectional"))
    )
    (net (code "53") (name "unconnected-(LED12-DOUT-Pad2)") (class "Default")
      (node (ref "LED12") (pin "2") (pinfunction "DOUT_2") (pintype "bidirectional"))
    )
    (net (code "54") (name "unconnected-(LED16-DOUT-Pad2)") (class "Default")
      (node (ref "LED16") (pin "2") (pinfunction "DOUT_2") (pintype "bidirectional"))
    )
    (net (code "55") (name "unconnected-(LED20-DOUT-Pad2)") (class "Default")
      (node (ref "LED20") (pin "2") (pinfunction "DOUT_2") (pintype "bidirectional"))
    )
    (net (code "56") (name "unconnected-(S1-MH-PadMH2)") (class "Default")
      (node (ref "S1") (pin "MH2") (pinfunction "MH_MH2") (pintype "bidirectional"))
    )
    (net (code "57") (name "unconnected-(S1-MH-PadMH3)") (class "Default")
      (node (ref "S1") (pin "MH3") (pinfunction "MH_MH3") (pintype "bidirectional"))
    )
    (net (code "58") (name "unconnected-(S2-MH-PadMH2)") (class "Default")
      (node (ref "S2") (pin "MH2") (pinfunction "MH_MH2") (pintype "bidirectional"))
    )
    (net (code "59") (name "unconnected-(S2-MH-PadMH3)") (class "Default")
      (node (ref "S2") (pin "MH3") (pinfunction "MH_MH3") (pintype "bidirectional"))
    )
    (net (code "60") (name "unconnected-(S3-MH-PadMH2)") (class "Default")
      (node (ref "S3") (pin "MH2") (pinfunction "MH_MH2") (pintype "bidirectional"))
    )
    (net (code "61") (name "unconnected-(S3-MH-PadMH3)") (class "Default")
      (node (ref "S3") (pin "MH3") (pinfunction "MH_MH3") (pintype "bidirectional"))
    )
    (net (code "62") (name "unconnected-(S4-MH-PadMH2)") (class "Default")
      (node (ref "S4") (pin "MH2") (pinfunction "MH_MH2") (pintype "bidirectional"))
    )
    (net (code "63") (name "unconnected-(S4-MH-PadMH3)") (class "Default")
      (node (ref "S4") (pin "MH3") (pinfunction "MH_MH3") (pintype "bidirectional"))
    )
    (net (code "64") (name "unconnected-(S5-MH-PadMH2)") (class "Default")
      (node (ref "S5") (pin "MH2") (pinfunction "MH_MH2") (pintype "bidirectional"))
    )
    (net (code "65") (name "unconnected-(S5-MH-PadMH3)") (class "Default")
      (node (ref "S5") (pin "MH3") (pinfunction "MH_MH3") (pintype "bidirectional"))
    )
    (net (code "66") (name "unconnected-(S6-MH-PadMH2)") (class "Default")
      (node (ref "S6") (pin "MH2") (pinfunction "MH_MH2") (pintype "bidirectional"))
    )
    (net (code "67") (name "unconnected-(S6-MH-PadMH3)") (class "Default")
      (node (ref "S6") (pin "MH3") (pinfunction "MH_MH3") (pintype "bidirectional"))
    )
    (net (code "68") (name "unconnected-(S7-MH-PadMH2)") (class "Default")
      (node (ref "S7") (pin "MH2") (pinfunction "MH_MH2") (pintype "bidirectional"))
    )
    (net (code "69") (name "unconnected-(S7-MH-PadMH3)") (class "Default")
      (node (ref "S7") (pin "MH3") (pinfunction "MH_MH3") (pintype "bidirectional"))
    )
    (net (code "70") (name "unconnected-(S8-MH-PadMH2)") (class "Default")
      (node (ref "S8") (pin "MH2") (pinfunction "MH_MH2") (pintype "bidirectional"))
    )
    (net (code "71") (name "unconnected-(S8-MH-PadMH3)") (class "Default")
      (node (ref "S8") (pin "MH3") (pinfunction "MH_MH3") (pintype "bidirectional"))
    )
    (net (code "72") (name "unconnected-(S9-MH-PadMH2)") (class "Default")
      (node (ref "S9") (pin "MH2") (pinfunction "MH_MH2") (pintype "bidirectional"))
    )
    (net (code "73") (name "unconnected-(S9-MH-PadMH3)") (class "Default")
      (node (ref "S9") (pin "MH3") (pinfunction "MH_MH3") (pintype "bidirectional"))
    )
    (net (code "74") (name "unconnected-(S10-MH-PadMH2)") (class "Default")
      (node (ref "S10") (pin "MH2") (pinfunction "MH_MH2") (pintype "bidirectional"))
    )
    (net (code "75") (name "unconnected-(S10-MH-PadMH3)") (class "Default")
      (node (ref "S10") (pin "MH3") (pinfunction "MH_MH3") (pintype "bidirectional"))
    )
    (net (code "76") (name "unconnected-(S11-MH-PadMH2)") (class "Default")
      (node (ref "S11") (pin "MH2") (pinfunction "MH_MH2") (pintype "bidirectional"))
    )
    (net (code "77") (name "unconnected-(S11-MH-PadMH3)") (class "Default")
      (node (ref "S11") (pin "MH3") (pinfunction "MH_MH3") (pintype "bidirectional"))
    )
    (net (code "78") (name "unconnected-(S12-MH-PadMH2)") (class "Default")
      (node (ref "S12") (pin "MH2") (pinfunction "MH_MH2") (pintype "bidirectional"))
    )
    (net (code "79") (name "unconnected-(S12-MH-PadMH3)") (class "Default")
      (node (ref "S12") (pin "MH3") (pinfunction "MH_MH3") (pintype "bidirectional"))
    )
    (net (code "80") (name "unconnected-(S13-MH-PadMH2)") (class "Default")
      (node (ref "S13") (pin "MH2") (pinfunction "MH_MH2") (pintype "bidirectional"))
    )
    (net (code "81") (name "unconnected-(S13-MH-PadMH3)") (class "Default")
      (node (ref "S13") (pin "MH3") (pinfunction "MH_MH3") (pintype "bidirectional"))
    )
    (net (code "82") (name "unconnected-(S14-MH-PadMH2)") (class "Default")
      (node (ref "S14") (pin "MH2") (pinfunction "MH_MH2") (pintype "bidirectional"))
    )
    (net (code "83") (name "unconnected-(S14-MH-PadMH3)") (class "Default")
      (node (ref "S14") (pin "MH3") (pinfunction "MH_MH3") (pintype "bidirectional"))
    )
    (net (code "84") (name "unconnected-(S15-MH-PadMH2)") (class "Default")
      (node (ref "S15") (pin "MH2") (pinfunction "MH_MH2") (pintype "bidirectional"))
    )
    (net (code "85") (name "unconnected-(S15-MH-PadMH3)") (class "Default")
      (node (ref "S15") (pin "MH3") (pinfunction "MH_MH3") (pintype "bidirectional"))
    )
    (net (code "86") (name "unconnected-(S16-MH-PadMH2)") (class "Default")
      (node (ref "S16") (pin "MH2") (pinfunction "MH_MH2") (pintype "bidirectional"))
    )
    (net (code "87") (name "unconnected-(S16-MH-PadMH3)") (class "Default")
      (node (ref "S16") (pin "MH3") (pinfunction "MH_MH3") (pintype "bidirectional"))
    )
    (net (code "88") (name "unconnected-(S17-MH-PadMH2)") (class "Default")
      (node (ref "S17") (pin "MH2") (pinfunction "MH_MH2") (pintype "bidirectional"))
    )
    (net (code "89") (name "unconnected-(S17-MH-PadMH3)") (class "Default")
      (node (ref "S17") (pin "MH3") (pinfunction "MH_MH3") (pintype "bidirectional"))
    )
    (net (code "90") (name "unconnected-(S18-MH-PadMH2)") (class "Default")
      (node (ref "S18") (pin "MH2") (pinfunction "MH_MH2") (pintype "bidirectional"))
    )
    (net (code "91") (name "unconnected-(S18-MH-PadMH3)") (class "Default")
      (node (ref "S18") (pin "MH3") (pinfunction "MH_MH3") (pintype "bidirectional"))
    )
    (net (code "92") (name "unconnected-(S19-MH-PadMH2)") (class "Default")
      (node (ref "S19") (pin "MH2") (pinfunction "MH_MH2") (pintype "bidirectional"))
    )
    (net (code "93") (name "unconnected-(S19-MH-PadMH3)") (class "Default")
      (node (ref "S19") (pin "MH3") (pinfunction "MH_MH3") (pintype "bidirectional"))
    )
    (net (code "94") (name "unconnected-(S20-MH-PadMH2)") (class "Default")
      (node (ref "S20") (pin "MH2") (pinfunction "MH_MH2") (pintype "bidirectional"))
    )
    (net (code "95") (name "unconnected-(S20-MH-PadMH3)") (class "Default")
      (node (ref "S20") (pin "MH3") (pinfunction "MH_MH3") (pintype "bidirectional"))
    )
    (net (code "96") (name "unconnected-(U$1-0-Pad3)") (class "Default")
      (node (ref "U$1") (pin "3") (pinfunction "0_3") (pintype "passive"))
    )
    (net (code "97") (name "unconnected-(U$1-1-Pad2)") (class "Default")
      (node (ref "U$1") (pin "2") (pinfunction "1_2") (pintype "passive"))
    )
    (net (code "98") (name "unconnected-(U$1-9-Pad23)") (class "Default")
      (node (ref "U$1") (pin "23") (pinfunction "9_23") (pintype "passive"))
    )
    (net (code "99") (name "unconnected-(U$1-10-Pad22)") (class "Default")
      (node (ref "U$1") (pin "22") (pinfunction "10_22") (pintype "passive"))
    )
    (net (code "100") (name "unconnected-(U$1-11-Pad21)") (class "Default")
      (node (ref "U$1") (pin "21") (pinfunction "11_21") (pintype "passive"))
    )
    (net (code "101") (name "unconnected-(U$1-12-Pad20)") (class "Default")
      (node (ref "U$1") (pin "20") (pinfunction "12_20") (pintype "passive"))
    )
    (net (code "102") (name "unconnected-(U$1-13-Pad19)") (class "Default")
      (node (ref "U$1") (pin "19") (pinfunction "13_19") (pintype "passive"))
    )
    (net (code "103") (name "unconnected-(U$1-A0-Pad12)") (class "Default")
      (node (ref "U$1") (pin "12") (pinfunction "A0_12") (pintype "passive"))
    )
    (net (code "104") (name "unconnected-(U$1-A1-Pad11)") (class "Default")
      (node (ref "U$1") (pin "11") (pinfunction "A1_11") (pintype "passive"))
    )
    (net (code "105") (name "unconnected-(U$1-A2-Pad10)") (class "Default")
      (node (ref "U$1") (pin "10") (pinfunction "A2_10") (pintype "passive"))
    )
    (net (code "106") (name "unconnected-(U$1-A3-Pad9)") (class "Default")
      (node (ref "U$1") (pin "9") (pinfunction "A3_9") (pintype "passive"))
    )
    (net (code "107") (name "unconnected-(U$1-A4-Pad8)") (class "Default")
      (node (ref "U$1") (pin "8") (pinfunction "A4_8") (pintype "passive"))
    )
    (net (code "108") (name "unconnected-(U$1-A5-Pad7)") (class "Default")
      (node (ref "U$1") (pin "7") (pinfunction "A5_7") (pintype "passive"))
    )
    (net (code "109") (name "unconnected-(U$1-AREF-Pad14)") (class "Default")
      (node (ref "U$1") (pin "14") (pinfunction "AREF_14") (pintype "passive"))
    )
    (net (code "110") (name "unconnected-(U$1-EN-Pad18)") (class "Default")
      (node (ref "U$1") (pin "18") (pinfunction "EN_18") (pintype "passive"))
    )
    (net (code "111") (name "unconnected-(U$1-GND-Pad13)") (class "Default")
      (node (ref "U$1") (pin "13") (pinfunction "GND_13") (pintype "passive"))
    )
    (net (code "112") (name "unconnected-(U$1-MISO-Pad4)") (class "Default")
      (node (ref "U$1") (pin "4") (pinfunction "MISO_4") (pintype "passive"))
    )
    (net (code "113") (name "unconnected-(U$1-MOSI-Pad5)") (class "Default")
      (node (ref "U$1") (pin "5") (pinfunction "MOSI_5") (pintype "passive"))
    )
    (net (code "114") (name "unconnected-(U$1-RST-Pad16)") (class "Default")
      (node (ref "U$1") (pin "16") (pinfunction "RST_16") (pintype "passive"))
    )
    (net (code "115") (name "unconnected-(U$1-SCK-Pad6)") (class "Default")
      (node (ref "U$1") (pin "6") (pinfunction "SCK_6") (pintype "passive"))
    )
    (net (code "116") (name "unconnected-(U$1-VBAT-Pad17)") (class "Default")
      (node (ref "U$1") (pin "17") (pinfunction "VBAT_17") (pintype "passive"))
    )
    (net (code "117") (name "unconnected-(U1-PadBAT+)") (class "Default")
      (node (ref "U1") (pin "BAT+") (pinfunction "BAT+_BAT+") (pintype "bidirectional"))
    )
    (net (code "118") (name "unconnected-(U1-PadBAT-)") (class "Default")
      (node (ref "U1") (pin "BAT-") (pinfunction "BAT-_BAT-") (pintype "bidirectional"))
    )
    (net (code "119") (name "unconnected-(X1-GND-PadGND@1)") (class "Default")
      (node (ref "X1") (pin "GND@1") (pinfunction "GND_GND@1") (pintype "bidirectional"))
    )
    (net (code "120") (name "unconnected-(X1-GND-PadGND@2)") (class "Default")
      (node (ref "X1") (pin "GND@2") (pinfunction "GND_GND@2") (pintype "bidirectional"))
    )
    (net (code "121") (name "unconnected-(X1-GND-PadGND@3)") (class "Default")
      (node (ref "X1") (pin "GND@3") (pinfunction "GND_GND@3") (pintype "bidirectional"))
    )
    (net (code "122") (name "unconnected-(X1-GND-PadGND@4)") (class "Default")
      (node (ref "X1") (pin "GND@4") (pinfunction "GND_GND@4") (pintype "bidirectional"))
    )
    (net (code "123") (name "unconnected-(X1-GND-PadGND@6)") (class "Default")
      (node (ref "X1") (pin "GND@6") (pinfunction "GND_GND@6") (pintype "bidirectional"))
    )
    (net (code "124") (name "unconnected-(X1-GND-PadGND@7)") (class "Default")
      (node (ref "X1") (pin "GND@7") (pinfunction "GND_GND@7") (pintype "bidirectional"))
    )
    (net (code "125") (name "unconnected-(X1-Pad3V3_EN)") (class "Default")
      (node (ref "X1") (pin "3V3_EN") (pinfunction "3V3_EN_3V3_EN") (pintype "bidirectional"))
    )
    (net (code "126") (name "unconnected-(X1-PadADC_VREF)") (class "Default")
      (node (ref "X1") (pin "ADC_VREF") (pinfunction "ADC_VREF_ADC_VREF") (pintype "bidirectional"))
    )
    (net (code "127") (name "unconnected-(X1-PadAGND)") (class "Default")
      (node (ref "X1") (pin "AGND") (pinfunction "AGND_AGND") (pintype "bidirectional"))
    )
    (net (code "128") (name "unconnected-(X1-PadGP2)") (class "Default")
      (node (ref "X1") (pin "GP2") (pinfunction "GP2_GP2") (pintype "bidirectional"))
    )
    (net (code "129") (name "unconnected-(X1-PadGP3)") (class "Default")
      (node (ref "X1") (pin "GP3") (pinfunction "GP3_GP3") (pintype "bidirectional"))
    )
    (net (code "130") (name "unconnected-(X1-PadGP6)") (class "Default")
      (node (ref "X1") (pin "GP6") (pinfunction "GP6_GP6") (pintype "bidirectional"))
    )
    (net (code "131") (name "unconnected-(X1-PadGP7)") (class "Default")
      (node (ref "X1") (pin "GP7") (pinfunction "GP7_GP7") (pintype "bidirectional"))
    )
    (net (code "132") (name "unconnected-(X1-PadGP8)") (class "Default")
      (node (ref "X1") (pin "GP8") (pinfunction "GP8_GP8") (pintype "bidirectional"))
    )
    (net (code "133") (name "unconnected-(X1-PadGP9)") (class "Default")
      (node (ref "X1") (pin "GP9") (pinfunction "GP9_GP9") (pintype "bidirectional"))
    )
    (net (code "134") (name "unconnected-(X1-PadGP10)") (class "Default")
      (node (ref "X1") (pin "GP10") (pinfunction "GP10_GP10") (pintype "bidirectional"))
    )
    (net (code "135") (name "unconnected-(X1-PadGP16)") (class "Default")
      (node (ref "X1") (pin "GP16") (pinfunction "GP16_GP16") (pintype "bidirectional"))
    )
    (net (code "136") (name "unconnected-(X1-PadGP17)") (class "Default")
      (node (ref "X1") (pin "GP17") (pinfunction "GP17_GP17") (pintype "bidirectional"))
    )
    (net (code "137") (name "unconnected-(X1-PadRUN)") (class "Default")
      (node (ref "X1") (pin "RUN") (pinfunction "RUN_RUN") (pintype "bidirectional"))
    )
  )
)
